# MCU.net
KiCad netlist of a schematic drawn in Altium Designer
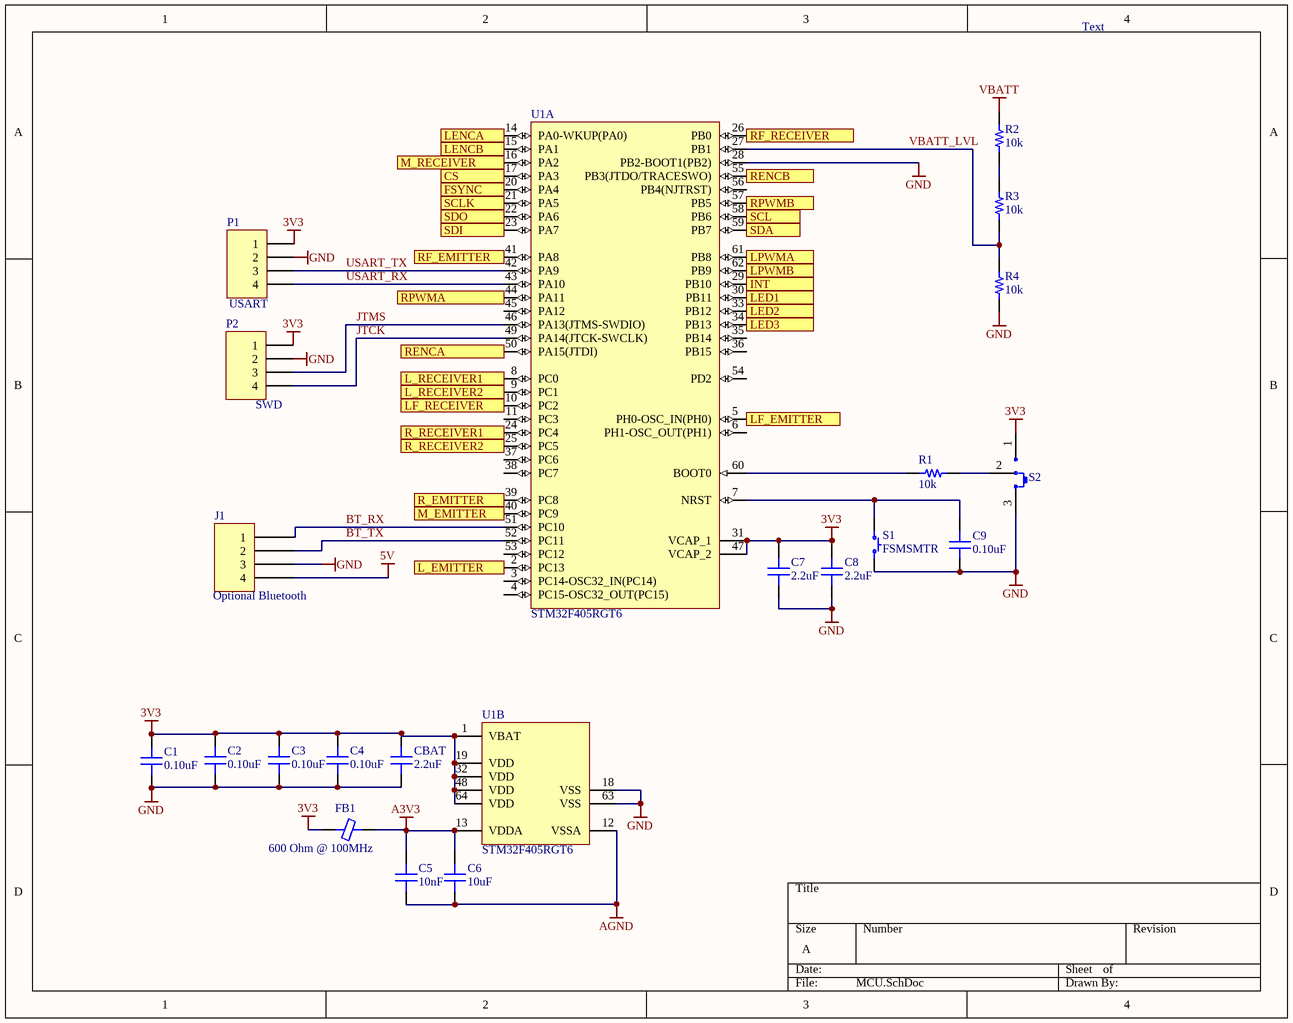
[diagram p0: MCU.SchDoc]

(export (version "E")
  (design (tool "Eeschema 10.0.6"))
  (components
    (comp (ref "C1")
      (value "0.10uF")
      (footprint "CAP 0402/1005")
      (description "CAP CER 0.1UF 16V X7R 0402")
      (fields
        (field (name "PART NUMBER") "GCM155R71C104KA55D")
        (field (name "MANUFACTURER") "Murata Electronics North America")
      )
      (libsource (lib "Celestial Library Database") (part "Capacitor"))
    )
    (comp (ref "C2")
      (value "0.10uF")
      (footprint "CAP 0402/1005")
      (description "CAP CER 0.1UF 16V X7R 0402")
      (fields
        (field (name "PART NUMBER") "GCM155R71C104KA55D")
        (field (name "MANUFACTURER") "Murata Electronics North America")
      )
      (libsource (lib "Celestial Library Database") (part "Capacitor"))
    )
    (comp (ref "C3")
      (value "0.10uF")
      (footprint "CAP 0402/1005")
      (description "CAP CER 0.1UF 16V X7R 0402")
      (fields
        (field (name "PART NUMBER") "GCM155R71C104KA55D")
        (field (name "MANUFACTURER") "Murata Electronics North America")
      )
      (libsource (lib "Celestial Library Database") (part "Capacitor"))
    )
    (comp (ref "C4")
      (value "0.10uF")
      (footprint "CAP 0402/1005")
      (description "CAP CER 0.1UF 16V X7R 0402")
      (fields
        (field (name "PART NUMBER") "GCM155R71C104KA55D")
        (field (name "MANUFACTURER") "Murata Electronics North America")
      )
      (libsource (lib "Celestial Library Database") (part "Capacitor"))
    )
    (comp (ref "C5")
      (value "10nF")
      (footprint "CAP 0402/1005")
      (description "CAP CER 10000PF 16V X7R 0402")
      (fields
        (field (name "PART NUMBER") "CL05B103KO5NNNC")
        (field (name "MANUFACTURER") "Samsung Electro-Mechanics America, Inc.")
      )
      (libsource (lib "Celestial Library Database") (part "Capacitor"))
    )
    (comp (ref "C6")
      (value "10uF")
      (footprint "CAP 0603/1608")
      (description "CAP CER 10UF 6.3V X5R 0603")
      (fields
        (field (name "PART NUMBER") "CL10A106MQ8NNNC")
        (field (name "MANUFACTURER") "Samsung Electro-Mechanics America, Inc.")
      )
      (libsource (lib "Celestial Library Database") (part "Capacitor"))
    )
    (comp (ref "C7")
      (value "2.2uF")
      (footprint "CAP 0402/1005")
      (description "CAP CER 2.2UF 10V X5R 0402")
      (fields
        (field (name "PART NUMBER") "CL05A225KP5NSNC")
        (field (name "MANUFACTURER") "Samsung Electro-Mechanics America, Inc.")
      )
      (libsource (lib "Celestial Library Database") (part "Capacitor"))
    )
    (comp (ref "C8")
      (value "2.2uF")
      (footprint "CAP 0402/1005")
      (description "CAP CER 2.2UF 10V X5R 0402")
      (fields
        (field (name "PART NUMBER") "CL05A225KP5NSNC")
        (field (name "MANUFACTURER") "Samsung Electro-Mechanics America, Inc.")
      )
      (libsource (lib "Celestial Library Database") (part "Capacitor"))
    )
    (comp (ref "C9")
      (value "0.10uF")
      (footprint "CAP 0402/1005")
      (description "CAP CER 0.1UF 16V X7R 0402")
      (fields
        (field (name "PART NUMBER") "GCM155R71C104KA55D")
        (field (name "MANUFACTURER") "Murata Electronics North America")
      )
      (libsource (lib "Celestial Library Database") (part "Capacitor"))
    )
    (comp (ref "CBAT")
      (value "2.2uF")
      (footprint "CAP 0402/1005")
      (description "CAP CER 2.2UF 10V X5R 0402")
      (fields
        (field (name "PART NUMBER") "CL05A225KP5NSNC")
        (field (name "MANUFACTURER") "Samsung Electro-Mechanics America, Inc.")
      )
      (libsource (lib "Celestial Library Database") (part "Capacitor"))
    )
    (comp (ref "FB1")
      (value "600 Ohm @ 100MHz")
      (footprint "FER 0603/1608")
      (description "FERRITE CHIP 300 OHM 500MA 0603")
      (fields (field (name "PART NUMBER") "BK1608HS601-T"))
      (libsource (lib "Celestial Library Database") (part "Ferrite Chip"))
    )
    (comp (ref "J1")
      (value "NPPN041BFCN-RC")
      (footprint "SULLINS NPPN041BFCN")
      (description "CONN RECEPT 2MM SINGLE STR 4POS")
      (fields (field (name "MANUFACTURER") "Sullins Connector Solutions"))
      (libsource (lib "Celestial Library Database") (part "4 Pin"))
    )
    (comp (ref "P1")
      (value "Header 4")
      (footprint "HDR1X4")
      (description "Header, 4-Pin")
      (fields (field (name "PUBLISHER") "Altium Limited"))
      (libsource (lib "Miscellaneous Connectors") (part "Header 4"))
    )
    (comp (ref "P2")
      (value "~")
      (footprint "HDR1X4")
      (description "Header, 4-Pin")
      (fields (field (name "PUBLISHER") "Altium Limited"))
      (libsource (lib "Miscellaneous Connectors") (part "Header 4"))
    )
    (comp (ref "R1")
      (value "10k")
      (footprint "RES 0402/1005")
      (description "RES SMD 10K OHM 5% 1/16W 0402")
      (fields (field (name "PART NUMBER") "RC0402JR-0710KL") (field (name "MANUFACTURER") "Yageo"))
      (libsource (lib "Celestial Library Database") (part "Resistor"))
    )
    (comp (ref "R2")
      (value "10k")
      (footprint "RES 0402/1005")
      (description "RES SMD 10K OHM 1% 1/10W 0402")
      (fields
        (field (name "PART NUMBER") "ERJ-2RKF1002X")
        (field (name "MANUFACTURER") "Panasonic Electronic Components")
      )
      (libsource (lib "Celestial Library Database") (part "Resistor"))
    )
    (comp (ref "R3")
      (value "10k")
      (footprint "RES 0402/1005")
      (description "RES SMD 10K OHM 1% 1/10W 0402")
      (fields
        (field (name "PART NUMBER") "ERJ-2RKF1002X")
        (field (name "MANUFACTURER") "Panasonic Electronic Components")
      )
      (libsource (lib "Celestial Library Database") (part "Resistor"))
    )
    (comp (ref "R4")
      (value "10k")
      (footprint "RES 0402/1005")
      (description "RES SMD 10K OHM 1% 1/10W 0402")
      (fields
        (field (name "PART NUMBER") "ERJ-2RKF1002X")
        (field (name "MANUFACTURER") "Panasonic Electronic Components")
      )
      (libsource (lib "Celestial Library Database") (part "Resistor"))
    )
    (comp (ref "S1")
      (value "FSMSMTR")
      (footprint "TE FSMSMTR")
      (description "SWITCH TACTILE SPST-NO 0.05A 24V")
      (fields (field (name "MANUFACTURER") "TE Connectivity Alcoswitch Switches"))
      (libsource (lib "Celestial Library Database") (part "SPST-NO 2 PIN"))
    )
    (comp (ref "S2")
      (value "SS312SAH4-R")
      (footprint "NKK SS312SAH4")
      (description "SWITCH SLIDE SPDT 0.4VA 28V")
      (fields (field (name "MANUFACTURER") "NKK Switches"))
      (libsource (lib "Celestial Library Database") (part "NKK SS312"))
    )
    (comp (ref "U1")
      (value "STM32F405RGT6")
      (footprint "STM-LQFP64_N")
      (fields (field (name "MANUFACTURER") "STMicroelectronics"))
      (libsource (lib "STMicroelectronics STM32 F4") (part "STM32F405RGT6"))
    )
  )
  (nets
    (net (code "1") (name "/BT_RX") (class "Default")
      (node (ref "J1") (pin "1") (pinfunction "1_1") (pintype "passive"))
      (node (ref "U1") (pin "51") (pinfunction "PC10_51") (pintype "bidirectional"))
    )
    (net (code "2") (name "/BT_TX") (class "Default")
      (node (ref "J1") (pin "2") (pinfunction "2_2") (pintype "passive"))
      (node (ref "U1") (pin "52") (pinfunction "PC11_52") (pintype "bidirectional"))
    )
    (net (code "3") (name "/CS") (class "Default")
      (node (ref "U1") (pin "17") (pinfunction "PA3_17") (pintype "bidirectional"))
    )
    (net (code "4") (name "/FSYNC") (class "Default")
      (node (ref "U1") (pin "20") (pinfunction "PA4_20") (pintype "bidirectional"))
    )
    (net (code "5") (name "/INT") (class "Default")
      (node (ref "U1") (pin "29") (pinfunction "PB10_29") (pintype "bidirectional"))
    )
    (net (code "6") (name "/JTCK") (class "Default")
      (node (ref "P2") (pin "4") (pinfunction "4_4") (pintype "passive"))
      (node (ref "U1") (pin "49") (pinfunction "PA14(JTCK-SWCLK)_49") (pintype "bidirectional"))
    )
    (net (code "8") (name "/JTMS") (class "Default")
      (node (ref "P2") (pin "3") (pinfunction "3_3") (pintype "passive"))
      (node (ref "U1") (pin "46") (pinfunction "PA13(JTMS-SWDIO)_46") (pintype "bidirectional"))
    )
    (net (code "9") (name "/LED1") (class "Default")
      (node (ref "U1") (pin "30") (pinfunction "PB11_30") (pintype "bidirectional"))
    )
    (net (code "10") (name "/LED2") (class "Default")
      (node (ref "U1") (pin "33") (pinfunction "PB12_33") (pintype "bidirectional"))
    )
    (net (code "11") (name "/LED3") (class "Default")
      (node (ref "U1") (pin "34") (pinfunction "PB13_34") (pintype "bidirectional"))
    )
    (net (code "12") (name "/LENCA") (class "Default")
      (node (ref "U1") (pin "14") (pinfunction "PA0-WKUP(PA0)_14") (pintype "bidirectional"))
    )
    (net (code "13") (name "/LENCB") (class "Default")
      (node (ref "U1") (pin "15") (pinfunction "PA1_15") (pintype "bidirectional"))
    )
    (net (code "14") (name "/LF_EMITTER") (class "Default")
      (node (ref "U1") (pin "5") (pinfunction "PH0-OSC_IN(PH0)_5") (pintype "bidirectional"))
    )
    (net (code "15") (name "/LF_RECEIVER") (class "Default")
      (node (ref "U1") (pin "10") (pinfunction "PC2_10") (pintype "bidirectional"))
    )
    (net (code "16") (name "/LPWMA") (class "Default")
      (node (ref "U1") (pin "61") (pinfunction "PB8_61") (pintype "bidirectional"))
    )
    (net (code "17") (name "/LPWMB") (class "Default")
      (node (ref "U1") (pin "62") (pinfunction "PB9_62") (pintype "bidirectional"))
    )
    (net (code "18") (name "/L_EMITTER") (class "Default")
      (node (ref "U1") (pin "2") (pinfunction "PC13_2") (pintype "bidirectional"))
    )
    (net (code "19") (name "/L_RECEIVER1") (class "Default")
      (node (ref "U1") (pin "8") (pinfunction "PC0_8") (pintype "bidirectional"))
    )
    (net (code "20") (name "/L_RECEIVER2") (class "Default")
      (node (ref "U1") (pin "9") (pinfunction "PC1_9") (pintype "bidirectional"))
    )
    (net (code "21") (name "/M_EMITTER") (class "Default")
      (node (ref "U1") (pin "40") (pinfunction "PC9_40") (pintype "bidirectional"))
    )
    (net (code "22") (name "/M_RECEIVER") (class "Default")
      (node (ref "U1") (pin "16") (pinfunction "PA2_16") (pintype "bidirectional"))
    )
    (net (code "23") (name "/RENCA") (class "Default")
      (node (ref "U1") (pin "50") (pinfunction "PA15(JTDI)_50") (pintype "bidirectional"))
    )
    (net (code "24") (name "/RENCB") (class "Default")
      (node (ref "U1") (pin "55") (pinfunction "PB3(JTDO/TRACESWO)_55") (pintype "bidirectional"))
    )
    (net (code "25") (name "/RF_EMITTER") (class "Default")
      (node (ref "U1") (pin "41") (pinfunction "PA8_41") (pintype "bidirectional"))
    )
    (net (code "26") (name "/RF_RECEIVER") (class "Default")
      (node (ref "U1") (pin "26") (pinfunction "PB0_26") (pintype "bidirectional"))
    )
    (net (code "27") (name "/RPWMA") (class "Default")
      (node (ref "U1") (pin "44") (pinfunction "PA11_44") (pintype "bidirectional"))
    )
    (net (code "28") (name "/RPWMB") (class "Default")
      (node (ref "U1") (pin "57") (pinfunction "PB5_57") (pintype "bidirectional"))
    )
    (net (code "29") (name "/R_EMITTER") (class "Default")
      (node (ref "U1") (pin "39") (pinfunction "PC8_39") (pintype "bidirectional"))
    )
    (net (code "30") (name "/R_RECEIVER1") (class "Default")
      (node (ref "U1") (pin "24") (pinfunction "PC4_24") (pintype "bidirectional"))
    )
    (net (code "31") (name "/R_RECEIVER2") (class "Default")
      (node (ref "U1") (pin "25") (pinfunction "PC5_25") (pintype "bidirectional"))
    )
    (net (code "32") (name "/SCL") (class "Default")
      (node (ref "U1") (pin "58") (pinfunction "PB6_58") (pintype "bidirectional"))
    )
    (net (code "33") (name "/SCLK") (class "Default")
      (node (ref "U1") (pin "21") (pinfunction "PA5_21") (pintype "bidirectional"))
    )
    (net (code "34") (name "/SDA") (class "Default")
      (node (ref "U1") (pin "59") (pinfunction "PB7_59") (pintype "bidirectional"))
    )
    (net (code "35") (name "/SDI") (class "Default")
      (node (ref "U1") (pin "23") (pinfunction "PA7_23") (pintype "bidirectional"))
    )
    (net (code "36") (name "/SDO") (class "Default")
      (node (ref "U1") (pin "22") (pinfunction "PA6_22") (pintype "bidirectional"))
    )
    (net (code "37") (name "/USART_RX") (class "Default")
      (node (ref "P1") (pin "4") (pinfunction "4_4") (pintype "passive"))
      (node (ref "U1") (pin "43") (pinfunction "PA10_43") (pintype "bidirectional"))
    )
    (net (code "38") (name "/USART_TX") (class "Default")
      (node (ref "P1") (pin "3") (pinfunction "3_3") (pintype "passive"))
      (node (ref "U1") (pin "42") (pinfunction "PA9_42") (pintype "bidirectional"))
    )
    (net (code "39") (name "/VBATT_LVL") (class "Default")
      (node (ref "R3") (pin "1") (pinfunction "1_1") (pintype "passive"))
      (node (ref "R4") (pin "2") (pinfunction "2_2") (pintype "passive"))
      (node (ref "U1") (pin "27") (pinfunction "PB1_27") (pintype "bidirectional"))
    )
    (net (code "40") (name "3V3") (class "Default")
      (node (ref "C1") (pin "2") (pinfunction "2_2") (pintype "passive"))
      (node (ref "C2") (pin "2") (pinfunction "2_2") (pintype "passive"))
      (node (ref "C3") (pin "2") (pinfunction "2_2") (pintype "passive"))
      (node (ref "C4") (pin "2") (pinfunction "2_2") (pintype "passive"))
      (node (ref "C7") (pin "2") (pinfunction "2_2") (pintype "passive"))
      (node (ref "C8") (pin "2") (pinfunction "2_2") (pintype "passive"))
      (node (ref "CBAT") (pin "2") (pinfunction "2_2") (pintype "passive"))
      (node (ref "FB1") (pin "2") (pinfunction "2_2") (pintype "passive"))
      (node (ref "P1") (pin "1") (pinfunction "1_1") (pintype "passive"))
      (node (ref "P2") (pin "1") (pinfunction "1_1") (pintype "passive"))
      (node (ref "S2") (pin "1") (pinfunction "1_1") (pintype "passive"))
      (node (ref "U1") (pin "1") (pinfunction "VBAT_1") (pintype "power_in"))
      (node (ref "U1") (pin "19") (pinfunction "VDD_19") (pintype "power_in"))
      (node (ref "U1") (pin "31") (pinfunction "VCAP_1_31") (pintype "power_in"))
      (node (ref "U1") (pin "32") (pinfunction "VDD_32") (pintype "power_in"))
      (node (ref "U1") (pin "47") (pinfunction "VCAP_2_47") (pintype "power_in"))
      (node (ref "U1") (pin "48") (pinfunction "VDD_48") (pintype "power_in"))
      (node (ref "U1") (pin "64") (pinfunction "VDD_64") (pintype "power_in"))
    )
    (net (code "41") (name "5V") (class "Default")
      (node (ref "J1") (pin "4") (pinfunction "4_4") (pintype "passive"))
    )
    (net (code "42") (name "A3V3") (class "Default")
      (node (ref "C5") (pin "2") (pinfunction "2_2") (pintype "passive"))
      (node (ref "C6") (pin "2") (pinfunction "2_2") (pintype "passive"))
      (node (ref "FB1") (pin "1") (pinfunction "1_1") (pintype "passive"))
      (node (ref "U1") (pin "13") (pinfunction "VDDA_13") (pintype "power_in"))
    )
    (net (code "43") (name "AGND") (class "Default")
      (node (ref "C5") (pin "1") (pinfunction "1_1") (pintype "passive"))
      (node (ref "C6") (pin "1") (pinfunction "1_1") (pintype "passive"))
      (node (ref "U1") (pin "12") (pinfunction "VSSA_12") (pintype "power_in"))
    )
    (net (code "44") (name "GND") (class "Default")
      (node (ref "C1") (pin "1") (pinfunction "1_1") (pintype "passive"))
      (node (ref "C2") (pin "1") (pinfunction "1_1") (pintype "passive"))
      (node (ref "C3") (pin "1") (pinfunction "1_1") (pintype "passive"))
      (node (ref "C4") (pin "1") (pinfunction "1_1") (pintype "passive"))
      (node (ref "C7") (pin "1") (pinfunction "1_1") (pintype "passive"))
      (node (ref "C8") (pin "1") (pinfunction "1_1") (pintype "passive"))
      (node (ref "C9") (pin "1") (pinfunction "1_1") (pintype "passive"))
      (node (ref "CBAT") (pin "1") (pinfunction "1_1") (pintype "passive"))
      (node (ref "J1") (pin "3") (pinfunction "3_3") (pintype "passive"))
      (node (ref "P1") (pin "2") (pinfunction "2_2") (pintype "passive"))
      (node (ref "P2") (pin "2") (pinfunction "2_2") (pintype "passive"))
      (node (ref "R4") (pin "1") (pinfunction "1_1") (pintype "passive"))
      (node (ref "S1") (pin "2") (pinfunction "2_2") (pintype "passive"))
      (node (ref "S2") (pin "3") (pinfunction "3_3") (pintype "passive"))
      (node (ref "U1") (pin "18") (pinfunction "VSS_18") (pintype "power_in"))
      (node (ref "U1") (pin "28") (pinfunction "PB2-BOOT1(PB2)_28") (pintype "bidirectional"))
      (node (ref "U1") (pin "63") (pinfunction "VSS_63") (pintype "power_in"))
    )
    (net (code "45") (name "Net-(R2-Pad1)") (class "Default")
      (node (ref "R2") (pin "1") (pinfunction "1_1") (pintype "passive"))
      (node (ref "R3") (pin "2") (pinfunction "2_2") (pintype "passive"))
    )
    (net (code "46") (name "Net-(S2-COM)") (class "Default")
      (node (ref "R1") (pin "2") (pinfunction "2_2") (pintype "passive"))
      (node (ref "S2") (pin "2") (pinfunction "COM_2") (pintype "passive"))
    )
    (net (code "47") (name "Net-(U1A-BOOT0)") (class "Default")
      (node (ref "R1") (pin "1") (pinfunction "1_1") (pintype "passive"))
      (node (ref "U1") (pin "60") (pinfunction "BOOT0_60") (pintype "input"))
    )
    (net (code "48") (name "Net-(U1A-NRST)") (class "Default")
      (node (ref "C9") (pin "2") (pinfunction "2_2") (pintype "passive"))
      (node (ref "S1") (pin "1") (pinfunction "1_1") (pintype "passive"))
      (node (ref "U1") (pin "7") (pinfunction "NRST_7") (pintype "bidirectional"))
    )
    (net (code "49") (name "VBATT") (class "Default")
      (node (ref "R2") (pin "2") (pinfunction "2_2") (pintype "passive"))
    )
    (net (code "50") (name "unconnected-(U1A-PA12-Pad45)") (class "Default")
      (node (ref "U1") (pin "45") (pinfunction "PA12_45") (pintype "bidirectional"))
    )
    (net (code "51") (name "unconnected-(U1A-PB4(NJTRST)-Pad56)") (class "Default")
      (node (ref "U1") (pin "56") (pinfunction "PB4(NJTRST)_56") (pintype "bidirectional"))
    )
    (net (code "52") (name "unconnected-(U1A-PB14-Pad35)") (class "Default")
      (node (ref "U1") (pin "35") (pinfunction "PB14_35") (pintype "bidirectional"))
    )
    (net (code "53") (name "unconnected-(U1A-PB15-Pad36)") (class "Default")
      (node (ref "U1") (pin "36") (pinfunction "PB15_36") (pintype "bidirectional"))
    )
    (net (code "54") (name "unconnected-(U1A-PC3-Pad11)") (class "Default")
      (node (ref "U1") (pin "11") (pinfunction "PC3_11") (pintype "bidirectional"))
    )
    (net (code "55") (name "unconnected-(U1A-PC6-Pad37)") (class "Default")
      (node (ref "U1") (pin "37") (pinfunction "PC6_37") (pintype "bidirectional"))
    )
    (net (code "56") (name "unconnected-(U1A-PC7-Pad38)") (class "Default")
      (node (ref "U1") (pin "38") (pinfunction "PC7_38") (pintype "bidirectional"))
    )
    (net (code "57") (name "unconnected-(U1A-PC12-Pad53)") (class "Default")
      (node (ref "U1") (pin "53") (pinfunction "PC12_53") (pintype "bidirectional"))
    )
    (net (code "58") (name "unconnected-(U1A-PC14-OSC32_IN(PC14)-Pad3)") (class "Default")
      (node (ref "U1") (pin "3") (pinfunction "PC14-OSC32_IN(PC14)_3") (pintype "bidirectional"))
    )
    (net (code "59") (name "unconnected-(U1A-PC15-OSC32_OUT(PC15)-Pad4)") (class "Default")
      (node (ref "U1") (pin "4") (pinfunction "PC15-OSC32_OUT(PC15)_4") (pintype "bidirectional"))
    )
    (net (code "60") (name "unconnected-(U1A-PD2-Pad54)") (class "Default")
      (node (ref "U1") (pin "54") (pinfunction "PD2_54") (pintype "bidirectional"))
    )
    (net (code "61") (name "unconnected-(U1A-PH1-OSC_OUT(PH1)-Pad6)") (class "Default")
      (node (ref "U1") (pin "6") (pinfunction "PH1-OSC_OUT(PH1)_6") (pintype "bidirectional"))
    )
  )
)
